# STAC_Test_Board_v1.net
KiCad netlist of a schematic drawn in Altium Designer
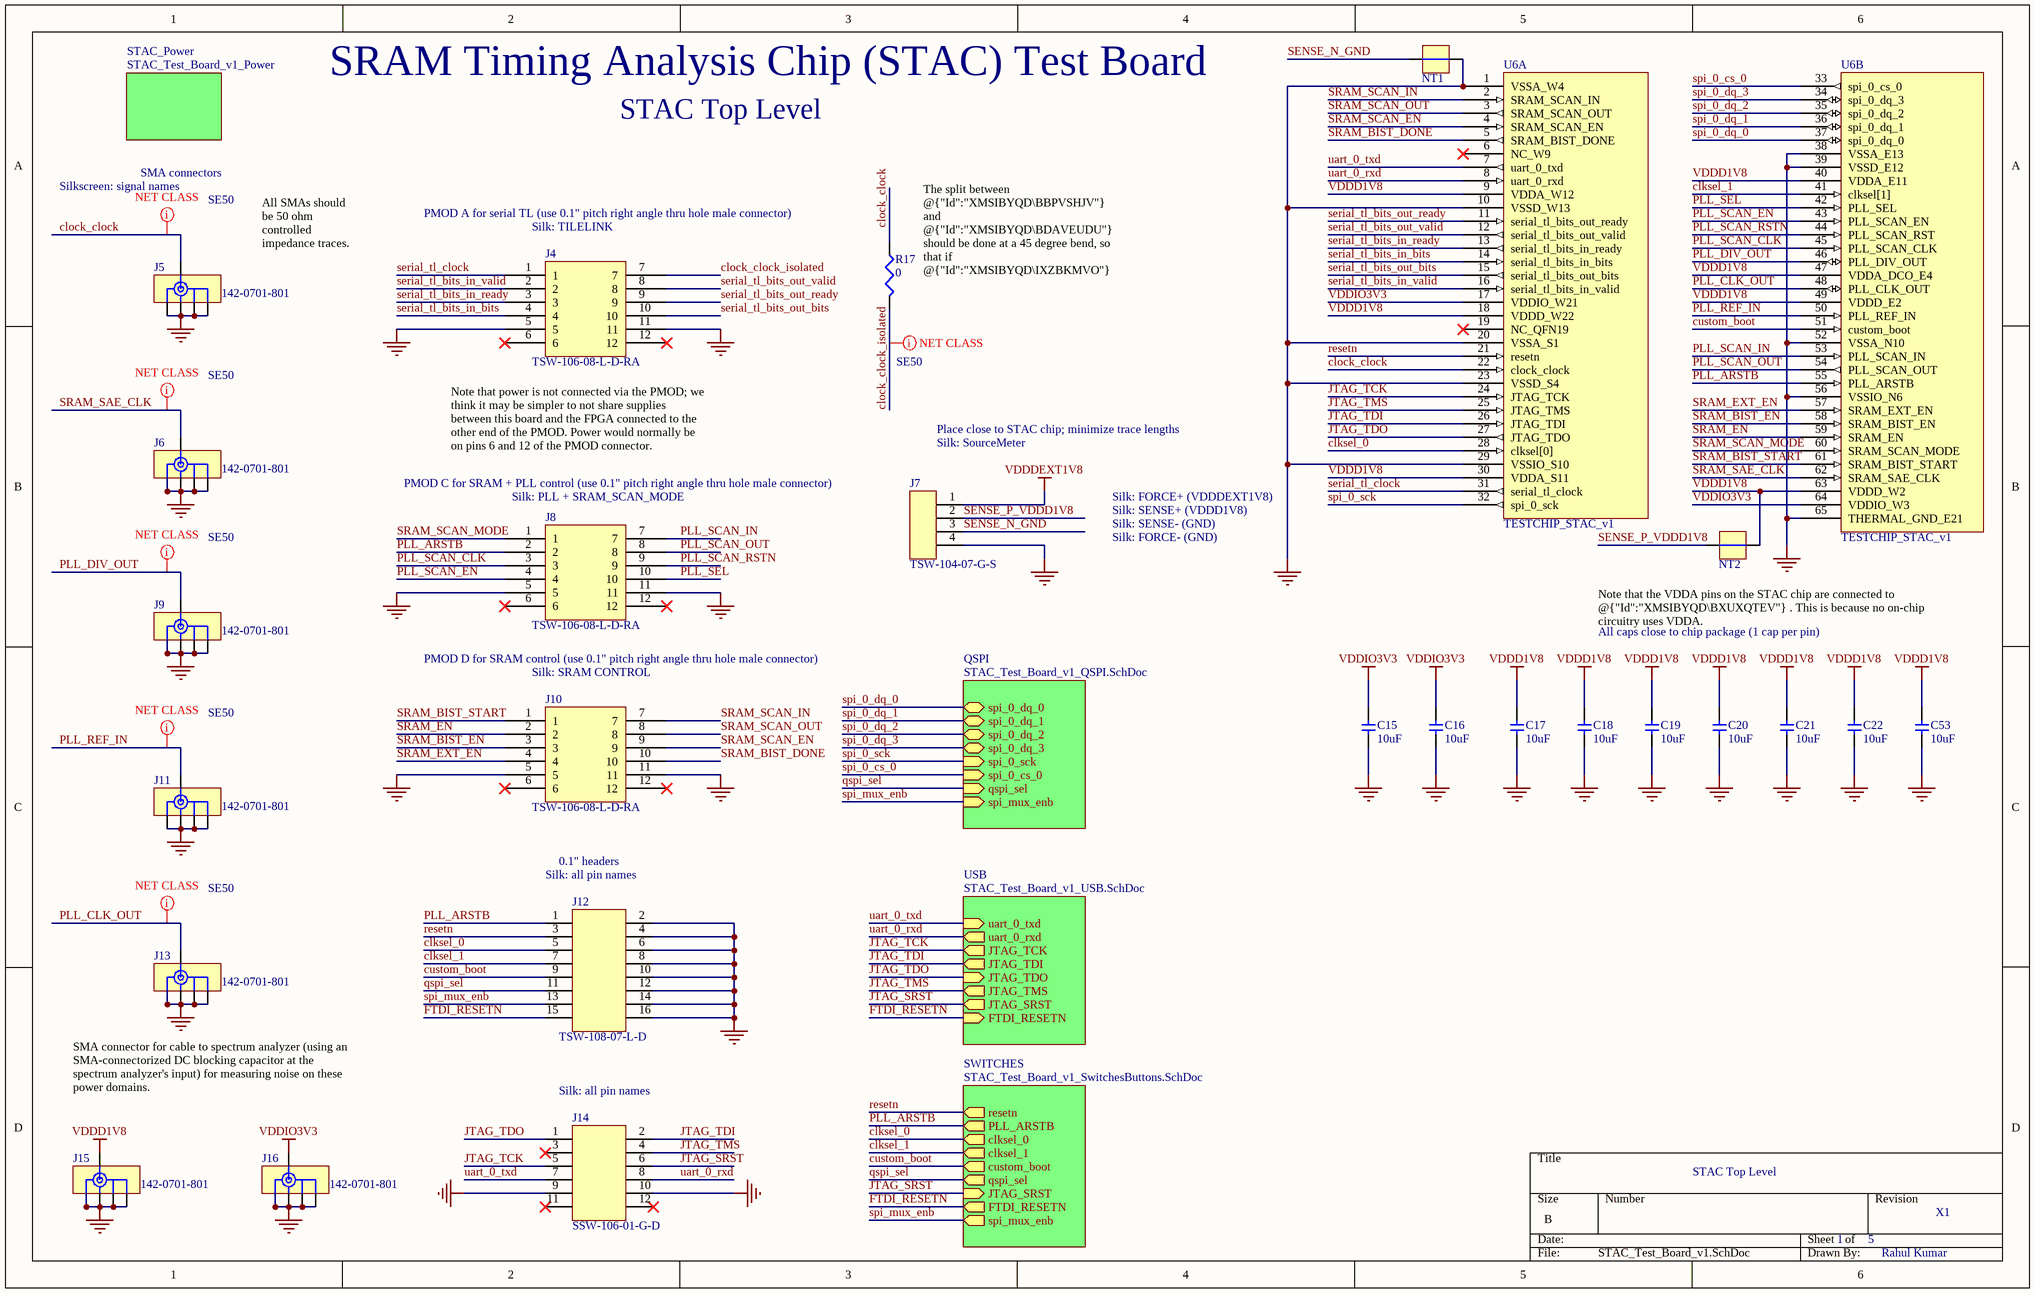
[diagram p0: STAC_Test_Board_v1.SchDoc]

(export (version "E")
  (design (tool "Eeschema 10.0.6"))
  (components
    (comp (ref "C15")
      (value "10uF")
      (footprint "0603")
      (description "Capacitor generic")
      (libsource (lib "BWRC") (part "DISCRETE_C"))
    )
    (comp (ref "C16")
      (value "10uF")
      (footprint "0603")
      (description "Capacitor generic")
      (libsource (lib "BWRC") (part "DISCRETE_C"))
    )
    (comp (ref "C17")
      (value "10uF")
      (footprint "0603")
      (description "Capacitor generic")
      (libsource (lib "BWRC") (part "DISCRETE_C"))
    )
    (comp (ref "C18")
      (value "10uF")
      (footprint "0603")
      (description "Capacitor generic")
      (libsource (lib "BWRC") (part "DISCRETE_C"))
    )
    (comp (ref "C19")
      (value "10uF")
      (footprint "0603")
      (description "Capacitor generic")
      (libsource (lib "BWRC") (part "DISCRETE_C"))
    )
    (comp (ref "C20")
      (value "10uF")
      (footprint "0603")
      (description "Capacitor generic")
      (libsource (lib "BWRC") (part "DISCRETE_C"))
    )
    (comp (ref "C21")
      (value "10uF")
      (footprint "0603")
      (description "Capacitor generic")
      (libsource (lib "BWRC") (part "DISCRETE_C"))
    )
    (comp (ref "C22")
      (value "10uF")
      (footprint "0603")
      (description "Capacitor generic")
      (libsource (lib "BWRC") (part "DISCRETE_C"))
    )
    (comp (ref "C53")
      (value "10uF")
      (footprint "0603")
      (description "Capacitor generic")
      (libsource (lib "BWRC") (part "DISCRETE_C"))
    )
    (comp (ref "J4")
      (value "TSW-106-08-L-D-RA")
      (footprint "BWRC:CON-012-100-600X200/2X6-POST-RA_alt")
      (description "Con 12 pins 2x6")
      (libsource (lib "") (part "CON_012pin_2x6_1"))
    )
    (comp (ref "J5")
      (value "142-0701-801")
      (footprint "CON-001-9.5X7.9/SMA-EDGE")
      (description "Con RF SMA")
      (libsource (lib "BWRC") (part "CON_RF_SMA"))
    )
    (comp (ref "J6")
      (value "142-0701-801")
      (footprint "CON-001-9.5X7.9/SMA-EDGE")
      (description "Con RF SMA")
      (libsource (lib "BWRC") (part "CON_RF_SMA"))
    )
    (comp (ref "J7")
      (value "TSW-104-07-G-S")
      (footprint "CON-004-100-400X100/1X4-POST")
      (description "Con 4 pins 1x4")
      (libsource (lib "BWRC") (part "CON_004pin_1x4"))
    )
    (comp (ref "J8")
      (value "TSW-106-08-L-D-RA")
      (footprint "CON-012-100-600X200/2X6-POST-RA_alt")
      (description "Con 12 pins 2x6")
      (libsource (lib "") (part "CON_012pin_2x6_1"))
    )
    (comp (ref "J9")
      (value "142-0701-801")
      (footprint "CON-001-9.5X7.9/SMA-EDGE")
      (description "Con RF SMA")
      (libsource (lib "BWRC") (part "CON_RF_SMA"))
    )
    (comp (ref "J10")
      (value "TSW-106-08-L-D-RA")
      (footprint "CON-012-100-600X200/2X6-POST-RA_alt")
      (description "Con 12 pins 2x6")
      (libsource (lib "") (part "CON_012pin_2x6_1"))
    )
    (comp (ref "J11")
      (value "142-0701-801")
      (footprint "CON-001-9.5X7.9/SMA-EDGE")
      (description "Con RF SMA")
      (libsource (lib "BWRC") (part "CON_RF_SMA"))
    )
    (comp (ref "J12")
      (value "TSW-108-07-L-D")
      (footprint "CON-016-100-800X200/2X8-POST")
      (description "Con 16 pins 2x8")
      (libsource (lib "BWRC") (part "CON_016pin_2x8"))
    )
    (comp (ref "J13")
      (value "142-0701-801")
      (footprint "CON-001-9.5X7.9/SMA-EDGE")
      (description "Con RF SMA")
      (libsource (lib "BWRC") (part "CON_RF_SMA"))
    )
    (comp (ref "J14")
      (value "SSW-106-01-G-D")
      (footprint "CON-012-100-600X200/2X6-POST")
      (description "Con 12 pins 2x6")
      (libsource (lib "BWRC") (part "CON_012pin_2x6"))
    )
    (comp (ref "J15")
      (value "142-0701-801")
      (footprint "CON-001-9.5X7.9/SMA-EDGE")
      (description "Con RF SMA")
      (libsource (lib "BWRC") (part "CON_RF_SMA"))
    )
    (comp (ref "J16")
      (value "142-0701-801")
      (footprint "CON-001-9.5X7.9/SMA-EDGE")
      (description "Con RF SMA")
      (libsource (lib "BWRC") (part "CON_RF_SMA"))
    )
    (comp (ref "NT1")
      (value "DISCRETE_NetTie")
      (footprint "NET_TIE_ALT2_10MIL")
      (description "Net tie")
      (libsource (lib "BWRC") (part "DISCRETE_NetTie"))
    )
    (comp (ref "NT2")
      (value "DISCRETE_NetTie")
      (footprint "NET_TIE_ALT2_10MIL")
      (description "Net tie")
      (libsource (lib "BWRC") (part "DISCRETE_NetTie"))
    )
    (comp (ref "R17")
      (value "0")
      (footprint "0603")
      (description "Resistor generic")
      (libsource (lib "BWRC") (part "DISCRETE_R"))
    )
    (comp (ref "U6")
      (value "TESTCHIP_STAC_v1")
      (footprint "QFN-64-.5-9.0X9.0/THERM-7.6")
      (description "TESTCHIP STAC v1")
      (libsource (lib "BWRC") (part "TESTCHIP_STAC_v1"))
    )
  )
  (nets
    (net (code "1") (name "/FTDI_RESETN") (class "Default")
      (node (ref "J12") (pin "15") (pinfunction "15_15") (pintype "passive"))
    )
    (net (code "2") (name "/JTAG_SRST") (class "Default")
      (node (ref "J14") (pin "6") (pinfunction "6_6") (pintype "passive"))
    )
    (net (code "3") (name "/JTAG_TCK") (class "Default")
      (node (ref "J14") (pin "5") (pinfunction "5_5") (pintype "passive"))
      (node (ref "U6") (pin "24") (pinfunction "JTAG_TCK_24") (pintype "input"))
    )
    (net (code "4") (name "/JTAG_TDI") (class "Default")
      (node (ref "J14") (pin "2") (pinfunction "2_2") (pintype "passive"))
      (node (ref "U6") (pin "26") (pinfunction "JTAG_TDI_26") (pintype "input"))
    )
    (net (code "5") (name "/JTAG_TDO") (class "Default")
      (node (ref "J14") (pin "1") (pinfunction "1_1") (pintype "passive"))
      (node (ref "U6") (pin "27") (pinfunction "JTAG_TDO_27") (pintype "output"))
    )
    (net (code "6") (name "/JTAG_TMS") (class "Default")
      (node (ref "J14") (pin "4") (pinfunction "4_4") (pintype "passive"))
      (node (ref "U6") (pin "25") (pinfunction "JTAG_TMS_25") (pintype "input"))
    )
    (net (code "7") (name "/PLL_ARSTB") (class "Default")
      (node (ref "J12") (pin "1") (pinfunction "1_1") (pintype "passive"))
      (node (ref "J8") (pin "2") (pinfunction "2_2") (pintype "passive"))
      (node (ref "U6") (pin "55") (pinfunction "PLL_ARSTB_55") (pintype "input"))
    )
    (net (code "8") (name "/PLL_CLK_OUT") (class "Default")
      (node (ref "J13") (pin "1") (pinfunction "1_1") (pintype "passive"))
      (node (ref "U6") (pin "48") (pinfunction "PLL_CLK_OUT_48") (pintype "bidirectional"))
    )
    (net (code "9") (name "/PLL_DIV_OUT") (class "Default")
      (node (ref "J9") (pin "1") (pinfunction "1_1") (pintype "passive"))
      (node (ref "U6") (pin "46") (pinfunction "PLL_DIV_OUT_46") (pintype "bidirectional"))
    )
    (net (code "10") (name "/PLL_REF_IN") (class "Default")
      (node (ref "J11") (pin "1") (pinfunction "1_1") (pintype "passive"))
      (node (ref "U6") (pin "50") (pinfunction "PLL_REF_IN_50") (pintype "input"))
    )
    (net (code "11") (name "/PLL_SCAN_CLK") (class "Default")
      (node (ref "J8") (pin "3") (pinfunction "3_3") (pintype "passive"))
      (node (ref "U6") (pin "45") (pinfunction "PLL_SCAN_CLK_45") (pintype "input"))
    )
    (net (code "12") (name "/PLL_SCAN_EN") (class "Default")
      (node (ref "J8") (pin "4") (pinfunction "4_4") (pintype "passive"))
      (node (ref "U6") (pin "43") (pinfunction "PLL_SCAN_EN_43") (pintype "input"))
    )
    (net (code "13") (name "/PLL_SCAN_IN") (class "Default")
      (node (ref "J8") (pin "7") (pinfunction "7_7") (pintype "passive"))
      (node (ref "U6") (pin "53") (pinfunction "PLL_SCAN_IN_53") (pintype "input"))
    )
    (net (code "14") (name "/PLL_SCAN_OUT") (class "Default")
      (node (ref "J8") (pin "8") (pinfunction "8_8") (pintype "passive"))
      (node (ref "U6") (pin "54") (pinfunction "PLL_SCAN_OUT_54") (pintype "output"))
    )
    (net (code "15") (name "/PLL_SCAN_RSTN") (class "Default")
      (node (ref "J8") (pin "9") (pinfunction "9_9") (pintype "passive"))
      (node (ref "U6") (pin "44") (pinfunction "PLL_SCAN_RST_44") (pintype "input"))
    )
    (net (code "16") (name "/PLL_SEL") (class "Default")
      (node (ref "J8") (pin "10") (pinfunction "10_10") (pintype "passive"))
      (node (ref "U6") (pin "42") (pinfunction "PLL_SEL_42") (pintype "input"))
    )
    (net (code "17") (name "/SENSE_N_GND") (class "Default")
      (node (ref "J7") (pin "3") (pinfunction "3_3") (pintype "passive"))
      (node (ref "NT1") (pin "1") (pinfunction "1_1") (pintype "passive"))
    )
    (net (code "18") (name "/SENSE_P_VDDD1V8") (class "Default")
      (node (ref "J7") (pin "2") (pinfunction "2_2") (pintype "passive"))
      (node (ref "NT2") (pin "1") (pinfunction "1_1") (pintype "passive"))
    )
    (net (code "19") (name "/SRAM_BIST_DONE") (class "Default")
      (node (ref "J10") (pin "10") (pinfunction "10_10") (pintype "passive"))
      (node (ref "U6") (pin "5") (pinfunction "SRAM_BIST_DONE_5") (pintype "output"))
    )
    (net (code "20") (name "/SRAM_BIST_EN") (class "Default")
      (node (ref "J10") (pin "3") (pinfunction "3_3") (pintype "passive"))
      (node (ref "U6") (pin "58") (pinfunction "SRAM_BIST_EN_58") (pintype "input"))
    )
    (net (code "21") (name "/SRAM_BIST_START") (class "Default")
      (node (ref "J10") (pin "1") (pinfunction "1_1") (pintype "passive"))
      (node (ref "U6") (pin "61") (pinfunction "SRAM_BIST_START_61") (pintype "input"))
    )
    (net (code "22") (name "/SRAM_EN") (class "Default")
      (node (ref "J10") (pin "2") (pinfunction "2_2") (pintype "passive"))
      (node (ref "U6") (pin "59") (pinfunction "SRAM_EN_59") (pintype "input"))
    )
    (net (code "23") (name "/SRAM_EXT_EN") (class "Default")
      (node (ref "J10") (pin "4") (pinfunction "4_4") (pintype "passive"))
      (node (ref "U6") (pin "57") (pinfunction "SRAM_EXT_EN_57") (pintype "input"))
    )
    (net (code "24") (name "/SRAM_SAE_CLK") (class "Default")
      (node (ref "J6") (pin "1") (pinfunction "1_1") (pintype "passive"))
      (node (ref "U6") (pin "62") (pinfunction "SRAM_SAE_CLK_62") (pintype "input"))
    )
    (net (code "25") (name "/SRAM_SCAN_EN") (class "Default")
      (node (ref "J10") (pin "9") (pinfunction "9_9") (pintype "passive"))
      (node (ref "U6") (pin "4") (pinfunction "SRAM_SCAN_EN_4") (pintype "input"))
    )
    (net (code "26") (name "/SRAM_SCAN_IN") (class "Default")
      (node (ref "J10") (pin "7") (pinfunction "7_7") (pintype "passive"))
      (node (ref "U6") (pin "2") (pinfunction "SRAM_SCAN_IN_2") (pintype "input"))
    )
    (net (code "27") (name "/SRAM_SCAN_MODE") (class "Default")
      (node (ref "J8") (pin "1") (pinfunction "1_1") (pintype "passive"))
      (node (ref "U6") (pin "60") (pinfunction "SRAM_SCAN_MODE_60") (pintype "input"))
    )
    (net (code "28") (name "/SRAM_SCAN_OUT") (class "Default")
      (node (ref "J10") (pin "8") (pinfunction "8_8") (pintype "passive"))
      (node (ref "U6") (pin "3") (pinfunction "SRAM_SCAN_OUT_3") (pintype "output"))
    )
    (net (code "29") (name "/clksel_0") (class "Default")
      (node (ref "J12") (pin "5") (pinfunction "5_5") (pintype "passive"))
      (node (ref "U6") (pin "28") (pinfunction "clksel[0]_28") (pintype "input"))
    )
    (net (code "30") (name "/clksel_1") (class "Default")
      (node (ref "J12") (pin "7") (pinfunction "7_7") (pintype "passive"))
      (node (ref "U6") (pin "41") (pinfunction "clksel[1]_41") (pintype "input"))
    )
    (net (code "31") (name "/clock_clock") (class "Default")
      (node (ref "J5") (pin "1") (pinfunction "1_1") (pintype "passive"))
      (node (ref "R17") (pin "1") (pinfunction "1_1") (pintype "passive"))
      (node (ref "U6") (pin "22") (pinfunction "clock_clock_22") (pintype "input"))
    )
    (net (code "32") (name "/clock_clock_isolated") (class "Default")
      (node (ref "J4") (pin "7") (pinfunction "7_7") (pintype "passive"))
      (node (ref "R17") (pin "2") (pinfunction "2_2") (pintype "passive"))
    )
    (net (code "33") (name "/custom_boot") (class "Default")
      (node (ref "J12") (pin "9") (pinfunction "9_9") (pintype "passive"))
      (node (ref "U6") (pin "51") (pinfunction "custom_boot_51") (pintype "input"))
    )
    (net (code "34") (name "/qspi_sel") (class "Default")
      (node (ref "J12") (pin "11") (pinfunction "11_11") (pintype "passive"))
    )
    (net (code "35") (name "/resetn") (class "Default")
      (node (ref "J12") (pin "3") (pinfunction "3_3") (pintype "passive"))
      (node (ref "U6") (pin "21") (pinfunction "resetn_21") (pintype "input"))
    )
    (net (code "36") (name "/serial_tl_bits_in_bits") (class "Default")
      (node (ref "J4") (pin "4") (pinfunction "4_4") (pintype "passive"))
      (node (ref "U6") (pin "14") (pinfunction "serial_tl_bits_in_bits_14") (pintype "input"))
    )
    (net (code "37") (name "/serial_tl_bits_in_ready") (class "Default")
      (node (ref "J4") (pin "3") (pinfunction "3_3") (pintype "passive"))
      (node (ref "U6") (pin "13") (pinfunction "serial_tl_bits_in_ready_13") (pintype "output"))
    )
    (net (code "38") (name "/serial_tl_bits_in_valid") (class "Default")
      (node (ref "J4") (pin "2") (pinfunction "2_2") (pintype "passive"))
      (node (ref "U6") (pin "16") (pinfunction "serial_tl_bits_in_valid_16") (pintype "input"))
    )
    (net (code "39") (name "/serial_tl_bits_out_bits") (class "Default")
      (node (ref "J4") (pin "10") (pinfunction "10_10") (pintype "passive"))
      (node (ref "U6") (pin "15") (pinfunction "serial_tl_bits_out_bits_15") (pintype "output"))
    )
    (net (code "40") (name "/serial_tl_bits_out_ready") (class "Default")
      (node (ref "J4") (pin "9") (pinfunction "9_9") (pintype "passive"))
      (node (ref "U6") (pin "11") (pinfunction "serial_tl_bits_out_ready_11") (pintype "input"))
    )
    (net (code "41") (name "/serial_tl_bits_out_valid") (class "Default")
      (node (ref "J4") (pin "8") (pinfunction "8_8") (pintype "passive"))
      (node (ref "U6") (pin "12") (pinfunction "serial_tl_bits_out_valid_12") (pintype "output"))
    )
    (net (code "42") (name "/serial_tl_clock") (class "Default")
      (node (ref "J4") (pin "1") (pinfunction "1_1") (pintype "passive"))
      (node (ref "U6") (pin "31") (pinfunction "serial_tl_clock_31") (pintype "output"))
    )
    (net (code "43") (name "/spi_0_cs_0") (class "Default")
      (node (ref "U6") (pin "33") (pinfunction "spi_0_cs_0_33") (pintype "output"))
    )
    (net (code "44") (name "/spi_0_dq_0") (class "Default")
      (node (ref "U6") (pin "37") (pinfunction "spi_0_dq_0_37") (pintype "bidirectional"))
    )
    (net (code "45") (name "/spi_0_dq_1") (class "Default")
      (node (ref "U6") (pin "36") (pinfunction "spi_0_dq_1_36") (pintype "bidirectional"))
    )
    (net (code "46") (name "/spi_0_dq_2") (class "Default")
      (node (ref "U6") (pin "35") (pinfunction "spi_0_dq_2_35") (pintype "bidirectional"))
    )
    (net (code "47") (name "/spi_0_dq_3") (class "Default")
      (node (ref "U6") (pin "34") (pinfunction "spi_0_dq_3_34") (pintype "bidirectional"))
    )
    (net (code "48") (name "/spi_0_sck") (class "Default")
      (node (ref "U6") (pin "32") (pinfunction "spi_0_sck_32") (pintype "output"))
    )
    (net (code "49") (name "/spi_mux_enb") (class "Default")
      (node (ref "J12") (pin "13") (pinfunction "13_13") (pintype "passive"))
    )
    (net (code "50") (name "/uart_0_rxd") (class "Default")
      (node (ref "J14") (pin "8") (pinfunction "8_8") (pintype "passive"))
      (node (ref "U6") (pin "8") (pinfunction "uart_0_rxd_8") (pintype "input"))
    )
    (net (code "51") (name "/uart_0_txd") (class "Default")
      (node (ref "J14") (pin "7") (pinfunction "7_7") (pintype "passive"))
      (node (ref "U6") (pin "7") (pinfunction "uart_0_txd_7") (pintype "output"))
    )
    (net (code "52") (name "GND") (class "Default")
      (node (ref "C15") (pin "2") (pinfunction "2_2") (pintype "passive"))
      (node (ref "C16") (pin "2") (pinfunction "2_2") (pintype "passive"))
      (node (ref "C17") (pin "2") (pinfunction "2_2") (pintype "passive"))
      (node (ref "C18") (pin "2") (pinfunction "2_2") (pintype "passive"))
      (node (ref "C19") (pin "2") (pinfunction "2_2") (pintype "passive"))
      (node (ref "C20") (pin "2") (pinfunction "2_2") (pintype "passive"))
      (node (ref "C21") (pin "2") (pinfunction "2_2") (pintype "passive"))
      (node (ref "C22") (pin "2") (pinfunction "2_2") (pintype "passive"))
      (node (ref "C53") (pin "2") (pinfunction "2_2") (pintype "passive"))
      (node (ref "J10") (pin "11") (pinfunction "11_11") (pintype "passive"))
      (node (ref "J10") (pin "5") (pinfunction "5_5") (pintype "passive"))
      (node (ref "J11") (pin "2") (pinfunction "2_2") (pintype "passive"))
      (node (ref "J11") (pin "3") (pinfunction "3_3") (pintype "passive"))
      (node (ref "J11") (pin "4") (pinfunction "4_4") (pintype "passive"))
      (node (ref "J11") (pin "5") (pinfunction "5_5") (pintype "passive"))
      (node (ref "J12") (pin "10") (pinfunction "10_10") (pintype "passive"))
      (node (ref "J12") (pin "12") (pinfunction "12_12") (pintype "passive"))
      (node (ref "J12") (pin "14") (pinfunction "14_14") (pintype "passive"))
      (node (ref "J12") (pin "16") (pinfunction "16_16") (pintype "passive"))
      (node (ref "J12") (pin "2") (pinfunction "2_2") (pintype "passive"))
      (node (ref "J12") (pin "4") (pinfunction "4_4") (pintype "passive"))
      (node (ref "J12") (pin "6") (pinfunction "6_6") (pintype "passive"))
      (node (ref "J12") (pin "8") (pinfunction "8_8") (pintype "passive"))
      (node (ref "J13") (pin "2") (pinfunction "2_2") (pintype "passive"))
      (node (ref "J13") (pin "3") (pinfunction "3_3") (pintype "passive"))
      (node (ref "J13") (pin "4") (pinfunction "4_4") (pintype "passive"))
      (node (ref "J13") (pin "5") (pinfunction "5_5") (pintype "passive"))
      (node (ref "J14") (pin "10") (pinfunction "10_10") (pintype "passive"))
      (node (ref "J14") (pin "9") (pinfunction "9_9") (pintype "passive"))
      (node (ref "J15") (pin "2") (pinfunction "2_2") (pintype "passive"))
      (node (ref "J15") (pin "3") (pinfunction "3_3") (pintype "passive"))
      (node (ref "J15") (pin "4") (pinfunction "4_4") (pintype "passive"))
      (node (ref "J15") (pin "5") (pinfunction "5_5") (pintype "passive"))
      (node (ref "J16") (pin "2") (pinfunction "2_2") (pintype "passive"))
      (node (ref "J16") (pin "3") (pinfunction "3_3") (pintype "passive"))
      (node (ref "J16") (pin "4") (pinfunction "4_4") (pintype "passive"))
      (node (ref "J16") (pin "5") (pinfunction "5_5") (pintype "passive"))
      (node (ref "J4") (pin "11") (pinfunction "11_11") (pintype "passive"))
      (node (ref "J4") (pin "5") (pinfunction "5_5") (pintype "passive"))
      (node (ref "J5") (pin "2") (pinfunction "2_2") (pintype "passive"))
      (node (ref "J5") (pin "3") (pinfunction "3_3") (pintype "passive"))
      (node (ref "J5") (pin "4") (pinfunction "4_4") (pintype "passive"))
      (node (ref "J5") (pin "5") (pinfunction "5_5") (pintype "passive"))
      (node (ref "J6") (pin "2") (pinfunction "2_2") (pintype "passive"))
      (node (ref "J6") (pin "3") (pinfunction "3_3") (pintype "passive"))
      (node (ref "J6") (pin "4") (pinfunction "4_4") (pintype "passive"))
      (node (ref "J6") (pin "5") (pinfunction "5_5") (pintype "passive"))
      (node (ref "J7") (pin "4") (pinfunction "4_4") (pintype "passive"))
      (node (ref "J8") (pin "11") (pinfunction "11_11") (pintype "passive"))
      (node (ref "J8") (pin "5") (pinfunction "5_5") (pintype "passive"))
      (node (ref "J9") (pin "2") (pinfunction "2_2") (pintype "passive"))
      (node (ref "J9") (pin "3") (pinfunction "3_3") (pintype "passive"))
      (node (ref "J9") (pin "4") (pinfunction "4_4") (pintype "passive"))
      (node (ref "J9") (pin "5") (pinfunction "5_5") (pintype "passive"))
      (node (ref "NT1") (pin "2") (pinfunction "2_2") (pintype "passive"))
      (node (ref "U6") (pin "1") (pinfunction "VSSA_W4_1") (pintype "power_in"))
      (node (ref "U6") (pin "10") (pinfunction "VSSD_W13_10") (pintype "power_in"))
      (node (ref "U6") (pin "20") (pinfunction "VSSA_S1_20") (pintype "power_in"))
      (node (ref "U6") (pin "23") (pinfunction "VSSD_S4_23") (pintype "power_in"))
      (node (ref "U6") (pin "29") (pinfunction "VSSIO_S10_29") (pintype "power_in"))
      (node (ref "U6") (pin "38") (pinfunction "VSSA_E13_38") (pintype "power_in"))
      (node (ref "U6") (pin "39") (pinfunction "VSSD_E12_39") (pintype "power_in"))
      (node (ref "U6") (pin "52") (pinfunction "VSSA_N10_52") (pintype "power_in"))
      (node (ref "U6") (pin "56") (pinfunction "VSSIO_N6_56") (pintype "power_in"))
      (node (ref "U6") (pin "65") (pinfunction "THERMAL_GND_E21_65") (pintype "power_in"))
    )
    (net (code "53") (name "VDDD1V8") (class "Default")
      (node (ref "C17") (pin "1") (pinfunction "1_1") (pintype "passive"))
      (node (ref "C18") (pin "1") (pinfunction "1_1") (pintype "passive"))
      (node (ref "C19") (pin "1") (pinfunction "1_1") (pintype "passive"))
      (node (ref "C20") (pin "1") (pinfunction "1_1") (pintype "passive"))
      (node (ref "C21") (pin "1") (pinfunction "1_1") (pintype "passive"))
      (node (ref "C22") (pin "1") (pinfunction "1_1") (pintype "passive"))
      (node (ref "C53") (pin "1") (pinfunction "1_1") (pintype "passive"))
      (node (ref "J15") (pin "1") (pinfunction "1_1") (pintype "passive"))
      (node (ref "NT2") (pin "2") (pinfunction "2_2") (pintype "passive"))
      (node (ref "U6") (pin "18") (pinfunction "VDDD_W22_18") (pintype "power_in"))
      (node (ref "U6") (pin "30") (pinfunction "VDDA_S11_30") (pintype "power_in"))
      (node (ref "U6") (pin "40") (pinfunction "VDDA_E11_40") (pintype "power_in"))
      (node (ref "U6") (pin "47") (pinfunction "VDDA_DCO_E4_47") (pintype "power_in"))
      (node (ref "U6") (pin "49") (pinfunction "VDDD_E2_49") (pintype "power_in"))
      (node (ref "U6") (pin "63") (pinfunction "VDDD_W2_63") (pintype "power_in"))
      (node (ref "U6") (pin "9") (pinfunction "VDDA_W12_9") (pintype "power_in"))
    )
    (net (code "54") (name "VDDDEXT1V8") (class "Default")
      (node (ref "J7") (pin "1") (pinfunction "1_1") (pintype "passive"))
    )
    (net (code "55") (name "VDDIO3V3") (class "Default")
      (node (ref "C15") (pin "1") (pinfunction "1_1") (pintype "passive"))
      (node (ref "C16") (pin "1") (pinfunction "1_1") (pintype "passive"))
      (node (ref "J16") (pin "1") (pinfunction "1_1") (pintype "passive"))
      (node (ref "U6") (pin "17") (pinfunction "VDDIO_W21_17") (pintype "power_in"))
      (node (ref "U6") (pin "64") (pinfunction "VDDIO_W3_64") (pintype "power_in"))
    )
    (net (code "56") (name "unconnected-(J4-Pad6)") (class "Default")
      (node (ref "J4") (pin "6") (pinfunction "6_6") (pintype "passive+no_connect"))
    )
    (net (code "57") (name "unconnected-(J4-Pad12)") (class "Default")
      (node (ref "J4") (pin "12") (pinfunction "12_12") (pintype "passive+no_connect"))
    )
    (net (code "58") (name "unconnected-(J8-Pad6)") (class "Default")
      (node (ref "J8") (pin "6") (pinfunction "6_6") (pintype "passive+no_connect"))
    )
    (net (code "59") (name "unconnected-(J8-Pad12)") (class "Default")
      (node (ref "J8") (pin "12") (pinfunction "12_12") (pintype "passive+no_connect"))
    )
    (net (code "60") (name "unconnected-(J10-Pad6)") (class "Default")
      (node (ref "J10") (pin "6") (pinfunction "6_6") (pintype "passive+no_connect"))
    )
    (net (code "61") (name "unconnected-(J10-Pad12)") (class "Default")
      (node (ref "J10") (pin "12") (pinfunction "12_12") (pintype "passive+no_connect"))
    )
    (net (code "62") (name "unconnected-(J14-Pad3)") (class "Default")
      (node (ref "J14") (pin "3") (pinfunction "3_3") (pintype "passive+no_connect"))
    )
    (net (code "63") (name "unconnected-(J14-Pad11)") (class "Default")
      (node (ref "J14") (pin "11") (pinfunction "11_11") (pintype "passive+no_connect"))
    )
    (net (code "64") (name "unconnected-(J14-Pad12)") (class "Default")
      (node (ref "J14") (pin "12") (pinfunction "12_12") (pintype "passive+no_connect"))
    )
    (net (code "65") (name "unconnected-(U6A-NC_QFN19-Pad19)") (class "Default")
      (node (ref "U6") (pin "19") (pinfunction "NC_QFN19_19") (pintype "tri_state+no_connect"))
    )
    (net (code "66") (name "unconnected-(U6A-NC_W9-Pad6)") (class "Default")
      (node (ref "U6") (pin "6") (pinfunction "NC_W9_6") (pintype "tri_state+no_connect"))
    )
  )
)
